# A4a_ESP32-WROOM-32.net
KiCad netlist of a schematic drawn in EAGLE
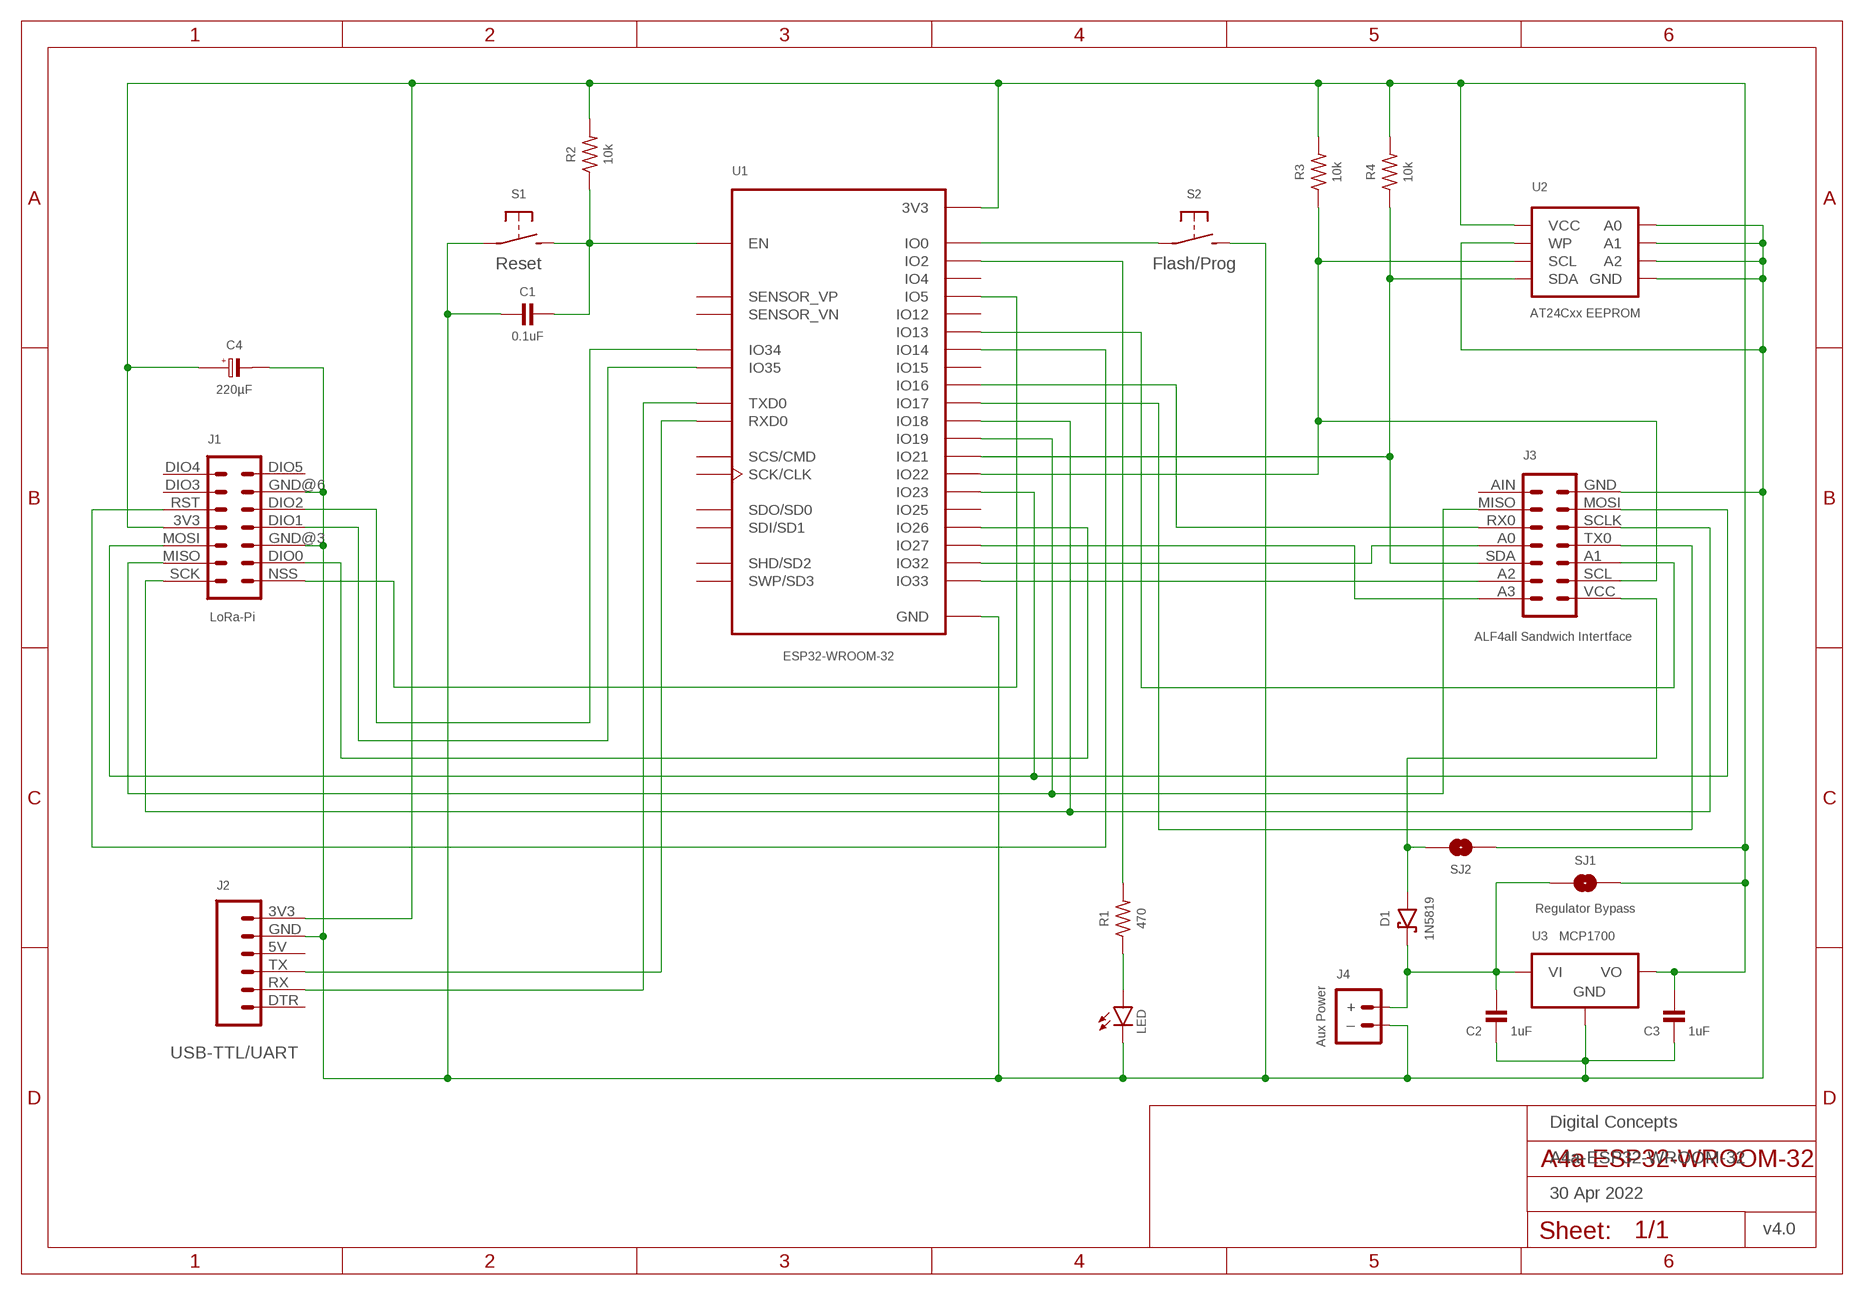
[diagram p0: schematic, sheet 1]

(export (version "E")
  (design (tool "Eeschema 10.0.6"))
  (components
    (comp (ref "C1")
      (value "0.1uF")
      (footprint "eagle-import:C0805@1")
      (libsource (lib "eagle-import") (part "CAPACITOR"))
    )
    (comp (ref "C2")
      (value "1uF")
      (footprint "eagle-import:C0805@1")
      (libsource (lib "eagle-import") (part "CAPACITOR"))
    )
    (comp (ref "C3")
      (value "1uF")
      (footprint "eagle-import:C0805@1")
      (libsource (lib "eagle-import") (part "CAPACITOR"))
    )
    (comp (ref "C4")
      (value "220µF")
      (footprint "eagle-import:C3528-21")
      (libsource (lib "eagle-import") (part "CAPACITOR-TANTALUM-3528"))
    )
    (comp (ref "D1")
      (value "1N5819")
      (footprint "eagle-import:SOD-123")
      (libsource (lib "eagle-import") (part "DIODE-SCHOTTKY-1N5819"))
    )
    (comp (ref "J1")
      (value "LoRa-Pi")
      (footprint "eagle-import:RFM95W-PI")
      (libsource (lib "eagle-import") (part "RFM95W-PI-HEADER"))
    )
    (comp (ref "J2")
      (value "USB-TTL/UART")
      (footprint "eagle-import:CONN_06-UART")
      (libsource (lib "eagle-import") (part "HEADER-1X6-UART"))
    )
    (comp (ref "J3")
      (value "ALF4all Sandwich Intertface")
      (footprint "eagle-import:CONN_2X7-ALF4ALL-PROCESSOR-B")
      (libsource (lib "eagle-import") (part "HEADER-2X7-ALF4ALL-PROCESSOR-B"))
    )
    (comp (ref "J4")
      (value "Aux Power")
      (footprint "eagle-import:JST-PH2.0-2-HORIZONTAL")
      (libsource (lib "eagle-import") (part "JST-PH2.0-2-MALE-HORIZONTALJST-PTH-2"))
    )
    (comp (ref "LED")
      (value "LEDCHIP-LED0805")
      (footprint "eagle-import:CHIP-LED0805")
      (libsource (lib "eagle-import") (part "LEDCHIP-LED0805"))
    )
    (comp (ref "R1")
      (value "470")
      (footprint "eagle-import:R0805")
      (libsource (lib "eagle-import") (part "RESISTORR0805"))
    )
    (comp (ref "R2")
      (value "10k")
      (footprint "eagle-import:R0805")
      (libsource (lib "eagle-import") (part "RESISTORR0805"))
    )
    (comp (ref "R3")
      (value "10k")
      (footprint "eagle-import:R0805")
      (libsource (lib "eagle-import") (part "RESISTORR0805"))
    )
    (comp (ref "R4")
      (value "10k")
      (footprint "eagle-import:R0805")
      (libsource (lib "eagle-import") (part "RESISTORR0805"))
    )
    (comp (ref "S1")
      (value "Reset")
      (footprint "eagle-import:SWITCH-2-PAD")
      (libsource (lib "eagle-import") (part "SWITCH-MOMENTARY-2-PIN"))
    )
    (comp (ref "S2")
      (value "Flash/Prog")
      (footprint "eagle-import:SWITCH-2-PAD")
      (libsource (lib "eagle-import") (part "SWITCH-MOMENTARY-2-PIN"))
    )
    (comp (ref "SJ1")
      (value "Regulator Bypass")
      (footprint "eagle-import:SJ")
      (libsource (lib "eagle-import") (part "SJ"))
    )
    (comp (ref "SJ2") (value "SJ") (footprint "eagle-import:SJ") (libsource (lib "eagle-import") (part "SJ")))
    (comp (ref "U1")
      (value "ESP32-WROOM-32")
      (footprint "eagle-import:ESP32-WROOM-32")
      (libsource (lib "eagle-import") (part "ESP32-WROOM-32"))
    )
    (comp (ref "U2")
      (value "AT24Cxx EEPROM")
      (footprint "eagle-import:SOP-8")
      (libsource (lib "eagle-import") (part "AT24CXX-EEPROM"))
    )
    (comp (ref "U3")
      (value "MCP1700")
      (footprint "eagle-import:SOT-23-3")
      (libsource (lib "eagle-import") (part "MCP1700"))
    )
  )
  (nets
    (net (code "1") (name "Net-(C4-+)") (class "Default")
      (node (ref "C3") (pin "1") (pinfunction "1_1") (pintype "passive"))
      (node (ref "C4") (pin "1") (pinfunction "+_1") (pintype "passive"))
      (node (ref "J1") (pin "3V3") (pinfunction "11_3V3") (pintype "passive"))
      (node (ref "J2") (pin "3V3") (pinfunction "6_3V3") (pintype "passive"))
      (node (ref "R2") (pin "2") (pinfunction "2_2") (pintype "passive"))
      (node (ref "R3") (pin "2") (pinfunction "2_2") (pintype "passive"))
      (node (ref "R4") (pin "2") (pinfunction "2_2") (pintype "passive"))
      (node (ref "SJ1") (pin "2") (pinfunction "2_2") (pintype "passive"))
      (node (ref "SJ2") (pin "2") (pinfunction "2_2") (pintype "passive"))
      (node (ref "U1") (pin "3V3") (pinfunction "3V3_3V3") (pintype "power_in"))
      (node (ref "U2") (pin "P$8") (pinfunction "VCC_P$8") (pintype "bidirectional"))
      (node (ref "U3") (pin "2") (pinfunction "VO_2") (pintype "output"))
    )
    (net (code "2") (name "Net-(C4--)") (class "Default")
      (node (ref "C1") (pin "2") (pinfunction "2_2") (pintype "passive"))
      (node (ref "C2") (pin "2") (pinfunction "2_2") (pintype "passive"))
      (node (ref "C3") (pin "2") (pinfunction "2_2") (pintype "passive"))
      (node (ref "C4") (pin "2") (pinfunction "-_2") (pintype "passive"))
      (node (ref "J1") (pin "GND@3") (pinfunction "3_GND@3") (pintype "passive"))
      (node (ref "J1") (pin "GND@6") (pinfunction "6_GND@6") (pintype "passive"))
      (node (ref "J2") (pin "GND") (pinfunction "5_GND") (pintype "passive"))
      (node (ref "J3") (pin "GND") (pinfunction "7_GND") (pintype "passive"))
      (node (ref "J4") (pin "-") (pinfunction "–_-") (pintype "power_in"))
      (node (ref "LED") (pin "C") (pinfunction "C_C") (pintype "passive"))
      (node (ref "S1") (pin "P$1") (pinfunction "P_P$1") (pintype "passive"))
      (node (ref "S2") (pin "P$2") (pinfunction "S_P$2") (pintype "passive"))
      (node (ref "U1") (pin "GND@1") (pinfunction "GND_GND@1") (pintype "power_in"))
      (node (ref "U1") (pin "GND@15") (pinfunction "GND_GND@15") (pintype "power_in"))
      (node (ref "U1") (pin "GND@38") (pinfunction "GND_GND@38") (pintype "power_in"))
      (node (ref "U1") (pin "TP") (pinfunction "GND_TP") (pintype "power_in"))
      (node (ref "U1") (pin "TP@P1") (pinfunction "GND_TP@P1") (pintype "power_in"))
      (node (ref "U1") (pin "TP@P2") (pinfunction "GND_TP@P2") (pintype "power_in"))
      (node (ref "U1") (pin "TP@P3") (pinfunction "GND_TP@P3") (pintype "power_in"))
      (node (ref "U1") (pin "TP@P4") (pinfunction "GND_TP@P4") (pintype "power_in"))
      (node (ref "U1") (pin "TP@P5") (pinfunction "GND_TP@P5") (pintype "power_in"))
      (node (ref "U1") (pin "TP@P6") (pinfunction "GND_TP@P6") (pintype "power_in"))
      (node (ref "U1") (pin "TP@P7") (pinfunction "GND_TP@P7") (pintype "power_in"))
      (node (ref "U1") (pin "TP@P8") (pinfunction "GND_TP@P8") (pintype "power_in"))
      (node (ref "U1") (pin "TP@P9") (pinfunction "GND_TP@P9") (pintype "power_in"))
      (node (ref "U1") (pin "TP@V1") (pinfunction "GND_TP@V1") (pintype "power_in"))
      (node (ref "U1") (pin "TP@V10") (pinfunction "GND_TP@V10") (pintype "power_in"))
      (node (ref "U1") (pin "TP@V11") (pinfunction "GND_TP@V11") (pintype "power_in"))
      (node (ref "U1") (pin "TP@V12") (pinfunction "GND_TP@V12") (pintype "power_in"))
      (node (ref "U1") (pin "TP@V2") (pinfunction "GND_TP@V2") (pintype "power_in"))
      (node (ref "U1") (pin "TP@V3") (pinfunction "GND_TP@V3") (pintype "power_in"))
      (node (ref "U1") (pin "TP@V4") (pinfunction "GND_TP@V4") (pintype "power_in"))
      (node (ref "U1") (pin "TP@V5") (pinfunction "GND_TP@V5") (pintype "power_in"))
      (node (ref "U1") (pin "TP@V6") (pinfunction "GND_TP@V6") (pintype "power_in"))
      (node (ref "U1") (pin "TP@V7") (pinfunction "GND_TP@V7") (pintype "power_in"))
      (node (ref "U1") (pin "TP@V8") (pinfunction "GND_TP@V8") (pintype "power_in"))
      (node (ref "U1") (pin "TP@V9") (pinfunction "GND_TP@V9") (pintype "power_in"))
      (node (ref "U1") (pin "TP@VP5") (pinfunction "GND_TP@VP5") (pintype "power_in"))
      (node (ref "U2") (pin "P$1") (pinfunction "A0_P$1") (pintype "bidirectional"))
      (node (ref "U2") (pin "P$2") (pinfunction "A1_P$2") (pintype "bidirectional"))
      (node (ref "U2") (pin "P$3") (pinfunction "A2_P$3") (pintype "bidirectional"))
      (node (ref "U2") (pin "P$4") (pinfunction "GND_P$4") (pintype "bidirectional"))
      (node (ref "U2") (pin "P$7") (pinfunction "WP_P$7") (pintype "bidirectional"))
      (node (ref "U3") (pin "1") (pinfunction "GND_1") (pintype "passive"))
    )
    (net (code "3") (name "Net-(J1-1)") (class "Default")
      (node (ref "J1") (pin "NSS") (pinfunction "1_NSS") (pintype "passive"))
      (node (ref "U1") (pin "IO5") (pinfunction "IO5_IO5") (pintype "bidirectional"))
    )
    (net (code "4") (name "Net-(J1-2)") (class "Default")
      (node (ref "J1") (pin "DIO0") (pinfunction "2_DIO0") (pintype "passive"))
      (node (ref "U1") (pin "IO26") (pinfunction "IO26_IO26") (pintype "bidirectional"))
    )
    (net (code "5") (name "Net-(J1-4)") (class "Default")
      (node (ref "J1") (pin "DIO1") (pinfunction "4_DIO1") (pintype "passive"))
      (node (ref "U1") (pin "IO35") (pinfunction "IO35_IO35") (pintype "input"))
    )
    (net (code "6") (name "Net-(J1-5)") (class "Default")
      (node (ref "J1") (pin "DIO2") (pinfunction "5_DIO2") (pintype "passive"))
      (node (ref "U1") (pin "IO34") (pinfunction "IO34_IO34") (pintype "input"))
    )
    (net (code "7") (name "Net-(J1-10)") (class "Default")
      (node (ref "J1") (pin "RST") (pinfunction "10_RST") (pintype "passive"))
      (node (ref "U1") (pin "IO14") (pinfunction "IO14_IO14") (pintype "bidirectional"))
    )
    (net (code "8") (name "Net-(J1-12)") (class "Default")
      (node (ref "J1") (pin "MOSI") (pinfunction "12_MOSI") (pintype "passive"))
      (node (ref "J3") (pin "MOSI") (pinfunction "6_MOSI") (pintype "passive"))
      (node (ref "U1") (pin "IO23") (pinfunction "IO23_IO23") (pintype "bidirectional"))
    )
    (net (code "9") (name "Net-(J1-13)") (class "Default")
      (node (ref "J1") (pin "MISO") (pinfunction "13_MISO") (pintype "passive"))
      (node (ref "J3") (pin "MISO") (pinfunction "9_MISO") (pintype "passive"))
      (node (ref "U1") (pin "IO19") (pinfunction "IO19_IO19") (pintype "bidirectional"))
    )
    (net (code "10") (name "Net-(J1-14)") (class "Default")
      (node (ref "J1") (pin "SCK") (pinfunction "14_SCK") (pintype "passive"))
      (node (ref "J3") (pin "SCLK") (pinfunction "5_SCLK") (pintype "passive"))
      (node (ref "U1") (pin "IO18") (pinfunction "IO18_IO18") (pintype "bidirectional"))
    )
    (net (code "11") (name "Net-(J2-2)") (class "Default")
      (node (ref "J2") (pin "RX") (pinfunction "2_RX") (pintype "passive"))
      (node (ref "U1") (pin "TXD0") (pinfunction "TXD0_TXD0") (pintype "bidirectional"))
    )
    (net (code "12") (name "Net-(J2-3)") (class "Default")
      (node (ref "J2") (pin "TX") (pinfunction "3_TX") (pintype "passive"))
      (node (ref "U1") (pin "RXD0") (pinfunction "RXD0_RXD0") (pintype "bidirectional"))
    )
    (net (code "13") (name "Net-(J3-1)") (class "Default")
      (node (ref "D1") (pin "A") (pinfunction "A_A") (pintype "passive"))
      (node (ref "J3") (pin "VCC") (pinfunction "1_VCC") (pintype "passive"))
      (node (ref "SJ2") (pin "1") (pinfunction "1_1") (pintype "passive"))
    )
    (net (code "14") (name "Net-(J3-2)") (class "Default")
      (node (ref "J3") (pin "SCL") (pinfunction "2_SCL") (pintype "passive"))
      (node (ref "R3") (pin "1") (pinfunction "1_1") (pintype "passive"))
      (node (ref "U1") (pin "IO22") (pinfunction "IO22_IO22") (pintype "bidirectional"))
      (node (ref "U2") (pin "P$6") (pinfunction "SCL_P$6") (pintype "bidirectional"))
    )
    (net (code "15") (name "Net-(J3-3)") (class "Default")
      (node (ref "J3") (pin "A1") (pinfunction "3_A1") (pintype "passive"))
      (node (ref "U1") (pin "IO13") (pinfunction "IO13_IO13") (pintype "bidirectional"))
    )
    (net (code "16") (name "Net-(J3-4)") (class "Default")
      (node (ref "J3") (pin "TX0") (pinfunction "4_TX0") (pintype "passive"))
      (node (ref "U1") (pin "IO17") (pinfunction "IO17_IO17") (pintype "bidirectional"))
    )
    (net (code "17") (name "Net-(J3-10)") (class "Default")
      (node (ref "J3") (pin "RX0") (pinfunction "10_RX0") (pintype "passive"))
      (node (ref "U1") (pin "IO16") (pinfunction "IO16_IO16") (pintype "bidirectional"))
    )
    (net (code "18") (name "Net-(J3-11)") (class "Default")
      (node (ref "J3") (pin "A0") (pinfunction "11_A0") (pintype "passive"))
      (node (ref "U1") (pin "IO32") (pinfunction "IO32_IO32") (pintype "bidirectional"))
    )
    (net (code "19") (name "Net-(J3-12)") (class "Default")
      (node (ref "J3") (pin "SDA") (pinfunction "12_SDA") (pintype "passive"))
      (node (ref "R4") (pin "1") (pinfunction "1_1") (pintype "passive"))
      (node (ref "U1") (pin "IO21") (pinfunction "IO21_IO21") (pintype "bidirectional"))
      (node (ref "U2") (pin "P$5") (pinfunction "SDA_P$5") (pintype "bidirectional"))
    )
    (net (code "20") (name "Net-(J3-13)") (class "Default")
      (node (ref "J3") (pin "A2") (pinfunction "13_A2") (pintype "passive"))
      (node (ref "U1") (pin "IO33") (pinfunction "IO33_IO33") (pintype "bidirectional"))
    )
    (net (code "21") (name "Net-(J3-14)") (class "Default")
      (node (ref "J3") (pin "A3") (pinfunction "14_A3") (pintype "passive"))
      (node (ref "U1") (pin "IO27") (pinfunction "IO27_IO27") (pintype "bidirectional"))
    )
    (net (code "22") (name "Net-(LED-PadA)") (class "Default")
      (node (ref "LED") (pin "A") (pinfunction "A_A") (pintype "passive"))
      (node (ref "R1") (pin "1") (pinfunction "1_1") (pintype "passive"))
    )
    (net (code "23") (name "Net-(R1-Pad2)") (class "Default")
      (node (ref "R1") (pin "2") (pinfunction "2_2") (pintype "passive"))
      (node (ref "U1") (pin "IO2") (pinfunction "IO2_IO2") (pintype "bidirectional"))
    )
    (net (code "24") (name "Net-(S1-S)") (class "Default")
      (node (ref "C1") (pin "1") (pinfunction "1_1") (pintype "passive"))
      (node (ref "R2") (pin "1") (pinfunction "1_1") (pintype "passive"))
      (node (ref "S1") (pin "P$2") (pinfunction "S_P$2") (pintype "passive"))
      (node (ref "U1") (pin "EN") (pinfunction "EN_EN") (pintype "input"))
    )
    (net (code "25") (name "Net-(S2-P)") (class "Default")
      (node (ref "S2") (pin "P$1") (pinfunction "P_P$1") (pintype "passive"))
      (node (ref "U1") (pin "IO0") (pinfunction "IO0_IO0") (pintype "bidirectional"))
    )
    (net (code "26") (name "Net-(U3-VI)") (class "Default")
      (node (ref "C2") (pin "1") (pinfunction "1_1") (pintype "passive"))
      (node (ref "D1") (pin "C") (pinfunction "C_C") (pintype "passive"))
      (node (ref "J4") (pin "+") (pinfunction "+_+") (pintype "power_in"))
      (node (ref "SJ1") (pin "1") (pinfunction "1_1") (pintype "passive"))
      (node (ref "U3") (pin "3") (pinfunction "VI_3") (pintype "input"))
    )
    (net (code "27") (name "unconnected-(J1-7-PadDIO5)") (class "Default")
      (node (ref "J1") (pin "DIO5") (pinfunction "7_DIO5") (pintype "passive"))
    )
    (net (code "28") (name "unconnected-(J1-8-PadDIO4)") (class "Default")
      (node (ref "J1") (pin "DIO4") (pinfunction "8_DIO4") (pintype "passive"))
    )
    (net (code "29") (name "unconnected-(J1-9-PadDIO3)") (class "Default")
      (node (ref "J1") (pin "DIO3") (pinfunction "9_DIO3") (pintype "passive"))
    )
    (net (code "30") (name "unconnected-(J2-1-PadDTR)") (class "Default")
      (node (ref "J2") (pin "DTR") (pinfunction "1_DTR") (pintype "passive"))
    )
    (net (code "31") (name "unconnected-(J2-4-Pad5V)") (class "Default")
      (node (ref "J2") (pin "5V") (pinfunction "4_5V") (pintype "passive"))
    )
    (net (code "32") (name "unconnected-(J3-8-PadAIN)") (class "Default")
      (node (ref "J3") (pin "AIN") (pinfunction "8_AIN") (pintype "passive"))
    )
    (net (code "33") (name "unconnected-(U1-PadIO4)") (class "Default")
      (node (ref "U1") (pin "IO4") (pinfunction "IO4_IO4") (pintype "bidirectional"))
    )
    (net (code "34") (name "unconnected-(U1-PadIO12)") (class "Default")
      (node (ref "U1") (pin "IO12") (pinfunction "IO12_IO12") (pintype "bidirectional"))
    )
    (net (code "35") (name "unconnected-(U1-PadIO15)") (class "Default")
      (node (ref "U1") (pin "IO15") (pinfunction "IO15_IO15") (pintype "bidirectional"))
    )
    (net (code "36") (name "unconnected-(U1-PadIO25)") (class "Default")
      (node (ref "U1") (pin "IO25") (pinfunction "IO25_IO25") (pintype "bidirectional"))
    )
    (net (code "37") (name "unconnected-(U1-PadSENSOR_VN)") (class "Default")
      (node (ref "U1") (pin "SENSOR_VN") (pinfunction "SENSOR_VN_SENSOR_VN") (pintype "input"))
    )
    (net (code "38") (name "unconnected-(U1-PadSENSOR_VP)") (class "Default")
      (node (ref "U1") (pin "SENSOR_VP") (pinfunction "SENSOR_VP_SENSOR_VP") (pintype "input"))
    )
    (net (code "39") (name "unconnected-(U1-SCK{slash}CLK-PadCLK)") (class "Default")
      (node (ref "U1") (pin "CLK") (pinfunction "SCK/CLK_CLK") (pintype "bidirectional"))
    )
    (net (code "40") (name "unconnected-(U1-SCS{slash}CMD-PadCMD)") (class "Default")
      (node (ref "U1") (pin "CMD") (pinfunction "SCS/CMD_CMD") (pintype "bidirectional"))
    )
    (net (code "41") (name "unconnected-(U1-SDI{slash}SD1-PadSD1)") (class "Default")
      (node (ref "U1") (pin "SD1") (pinfunction "SDI/SD1_SD1") (pintype "bidirectional"))
    )
    (net (code "42") (name "unconnected-(U1-SDO{slash}SD0-PadSD0)") (class "Default")
      (node (ref "U1") (pin "SD0") (pinfunction "SDO/SD0_SD0") (pintype "bidirectional"))
    )
    (net (code "43") (name "unconnected-(U1-SHD{slash}SD2-PadSD2)") (class "Default")
      (node (ref "U1") (pin "SD2") (pinfunction "SHD/SD2_SD2") (pintype "bidirectional"))
    )
    (net (code "44") (name "unconnected-(U1-SWP{slash}SD3-PadSD3)") (class "Default")
      (node (ref "U1") (pin "SD3") (pinfunction "SWP/SD3_SD3") (pintype "bidirectional"))
    )
  )
)
